# BSE_APPS_Error_Detection.net
KiCad netlist of a schematic drawn in EAGLE
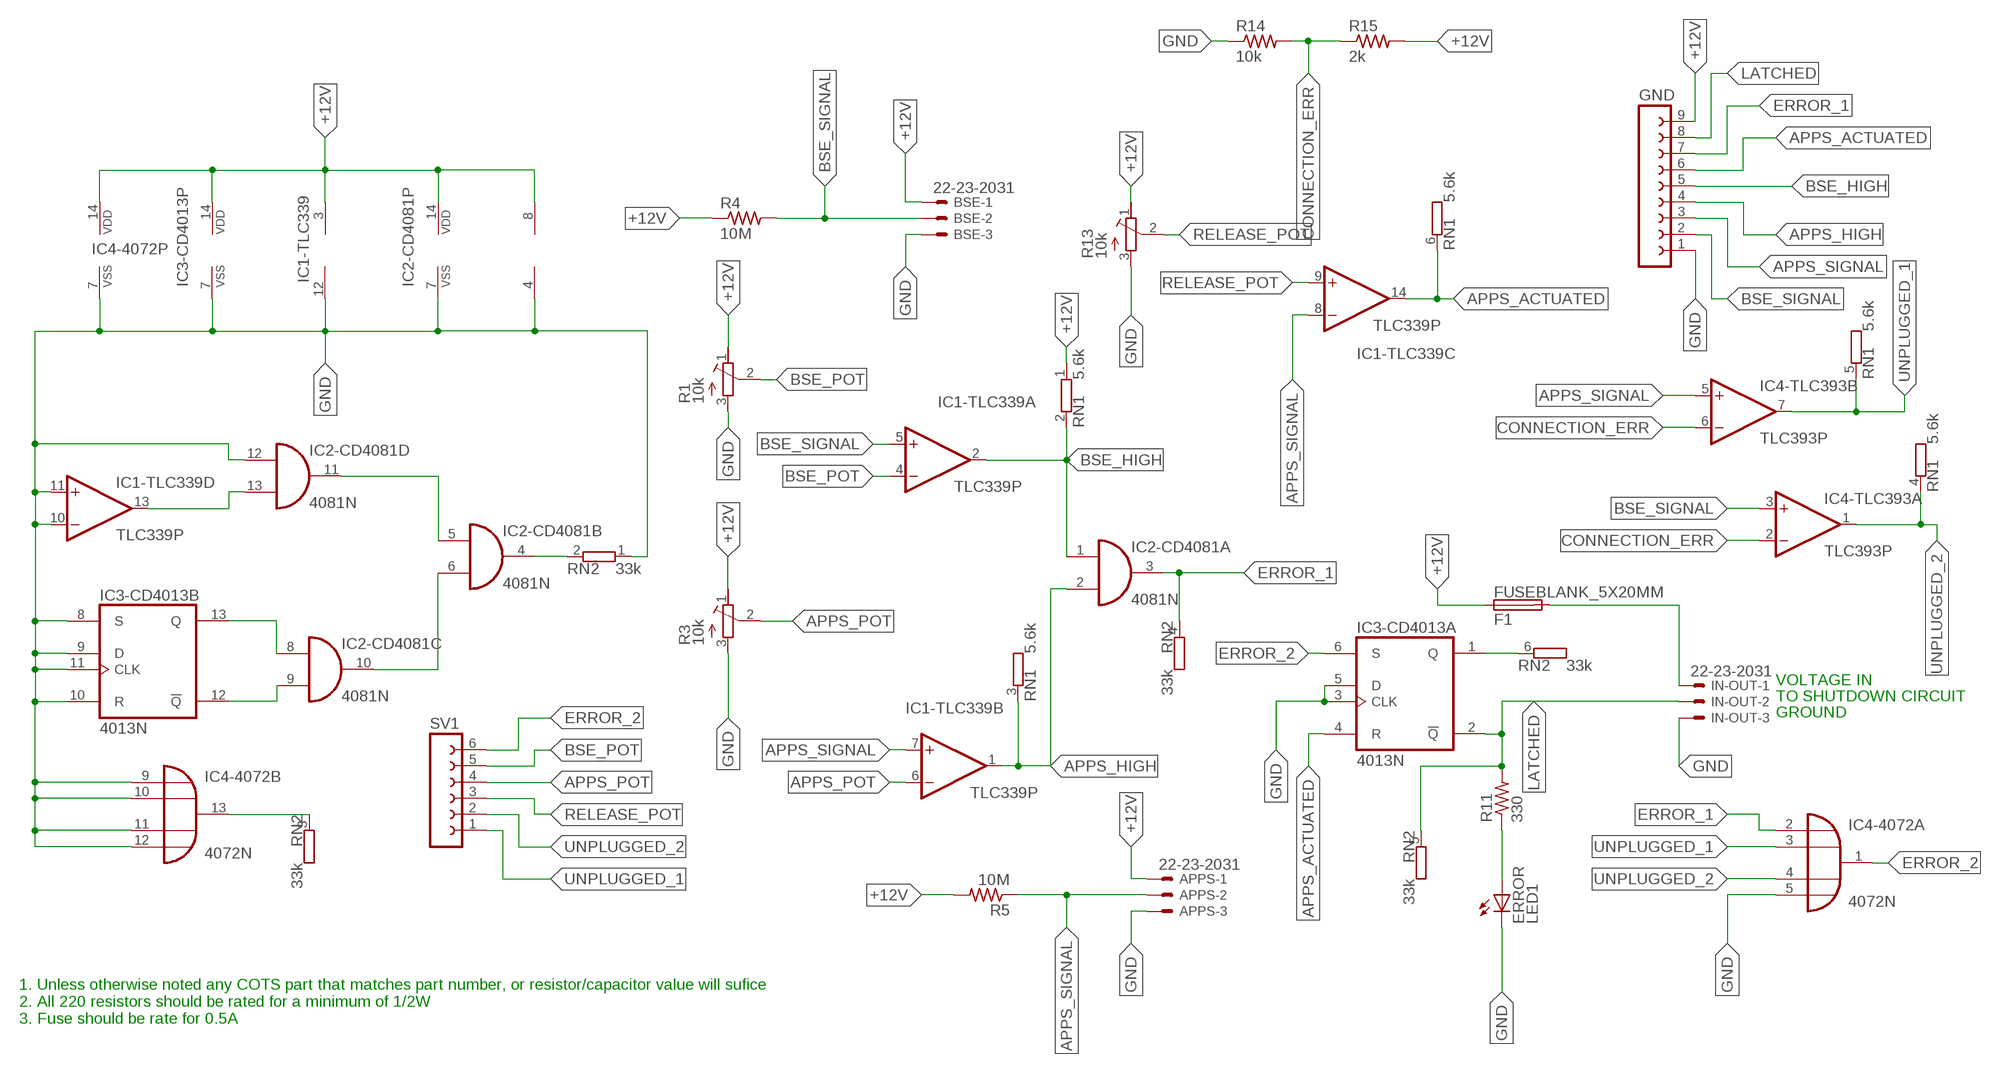
[diagram p0: schematic, sheet 1]

(export (version "E")
  (design (tool "Eeschema 10.0.6"))
  (components
    (comp (ref "APPS")
      (value "22-23-2031")
      (footprint "eagle-import:22-23-2031")
      (fields (field (name "MF") "MOLEX"))
      (libsource (lib "eagle-import") (part "22-23-2031"))
    )
    (comp (ref "BSE")
      (value "22-23-2031")
      (footprint "eagle-import:22-23-2031")
      (fields (field (name "MF") "MOLEX"))
      (libsource (lib "eagle-import") (part "22-23-2031"))
    )
    (comp (ref "ERROR")
      (value "LED1")
      (footprint "eagle-import:LED5MM")
      (libsource (lib "eagle-import") (part "LED5MM"))
    )
    (comp (ref "F1")
      (value "FUSEBLANK_5X20MM")
      (footprint "eagle-import:FUSE_HOLDER_5X20MM")
      (libsource (lib "eagle-import") (part "FUSEBLANK_5X20MM"))
    )
    (comp (ref "GND")
      (value "FE09W")
      (footprint "eagle-import:FE09W")
      (libsource (lib "eagle-import") (part "FE09W"))
    )
    (comp (ref "IC1-TLC339")
      (value "TLC339P")
      (footprint "eagle-import:DIL14")
      (libsource (lib "eagle-import") (part "TLC339P"))
    )
    (comp (ref "IC2-CD4081")
      (value "4081N")
      (footprint "eagle-import:DIL14")
      (libsource (lib "eagle-import") (part "4081N"))
    )
    (comp (ref "IC3-CD4013")
      (value "4013N")
      (footprint "eagle-import:DIL14")
      (libsource (lib "eagle-import") (part "4013N"))
    )
    (comp (ref "IC4-4072")
      (value "4072N")
      (footprint "eagle-import:DIL14")
      (libsource (lib "eagle-import") (part "4072N"))
    )
    (comp (ref "IC4-TLC393")
      (value "TLC393P")
      (footprint "eagle-import:DIL08")
      (libsource (lib "eagle-import") (part "TLC393P"))
    )
    (comp (ref "IN-OUT")
      (value "22-23-2031")
      (footprint "eagle-import:22-23-2031")
      (fields (field (name "MF") "MOLEX"))
      (libsource (lib "eagle-import") (part "22-23-2031"))
    )
    (comp (ref "R1")
      (value "10k")
      (footprint "eagle-import:RTRIM3006P")
      (libsource (lib "eagle-import") (part "R-TRIMM3006P"))
    )
    (comp (ref "R3")
      (value "10k")
      (footprint "eagle-import:RTRIM3006P")
      (libsource (lib "eagle-import") (part "R-TRIMM3006P"))
    )
    (comp (ref "R4")
      (value "10M")
      (footprint "eagle-import:0207_10")
      (libsource (lib "eagle-import") (part "R-US_0207/10"))
    )
    (comp (ref "R5")
      (value "10M")
      (footprint "eagle-import:0207_10")
      (libsource (lib "eagle-import") (part "R-US_0207/10"))
    )
    (comp (ref "R11")
      (value "330")
      (footprint "eagle-import:0207_10")
      (libsource (lib "eagle-import") (part "R-US_0207/10"))
    )
    (comp (ref "R13")
      (value "10k")
      (footprint "eagle-import:RTRIM3006P")
      (libsource (lib "eagle-import") (part "R-TRIMM3006P"))
    )
    (comp (ref "R14")
      (value "10k")
      (footprint "eagle-import:0207_10")
      (libsource (lib "eagle-import") (part "R-US_0207/10"))
    )
    (comp (ref "R15")
      (value "2k")
      (footprint "eagle-import:0207_10")
      (libsource (lib "eagle-import") (part "R-US_0207/10"))
    )
    (comp (ref "RN1")
      (value "5.6k")
      (footprint "eagle-import:SIL6")
      (libsource (lib "eagle-import") (part "GE05RP"))
    )
    (comp (ref "RN2")
      (value "33k")
      (footprint "eagle-import:SIL6")
      (libsource (lib "eagle-import") (part "GE05RP"))
    )
    (comp (ref "SV1")
      (value "FE06W")
      (footprint "eagle-import:FE06W")
      (libsource (lib "eagle-import") (part "FE06W"))
    )
  )
  (nets
    (net (code "1") (name "+12V") (class "Default")
      (node (ref "APPS") (pin "1") (pinfunction "S_1") (pintype "passive"))
      (node (ref "BSE") (pin "1") (pinfunction "S_1") (pintype "passive"))
      (node (ref "F1") (pin "1") (pinfunction "1_1") (pintype "passive"))
      (node (ref "GND") (pin "9") (pinfunction "9_9") (pintype "passive"))
      (node (ref "IC1-TLC339") (pin "3") (pinfunction "V+_3") (pintype "power_in"))
      (node (ref "IC2-CD4081") (pin "14") (pinfunction "VDD_14") (pintype "power_in"))
      (node (ref "IC3-CD4013") (pin "14") (pinfunction "VDD_14") (pintype "power_in"))
      (node (ref "IC4-4072") (pin "14") (pinfunction "VDD_14") (pintype "power_in"))
      (node (ref "IC4-TLC393") (pin "8") (pinfunction "V+_8") (pintype "power_in"))
      (node (ref "R1") (pin "1") (pinfunction "E_1") (pintype "passive"))
      (node (ref "R13") (pin "1") (pinfunction "E_1") (pintype "passive"))
      (node (ref "R15") (pin "2") (pinfunction "2_2") (pintype "passive"))
      (node (ref "R3") (pin "1") (pinfunction "E_1") (pintype "passive"))
      (node (ref "R4") (pin "1") (pinfunction "1_1") (pintype "passive"))
      (node (ref "R5") (pin "2") (pinfunction "2_2") (pintype "passive"))
      (node (ref "RN1") (pin "1") (pinfunction "1_1") (pintype "passive"))
    )
    (net (code "2") (name "APPS_ACTUATED") (class "Default")
      (node (ref "GND") (pin "6") (pinfunction "6_6") (pintype "passive"))
      (node (ref "IC1-TLC339") (pin "14") (pinfunction "OUT_14") (pintype "output"))
      (node (ref "IC3-CD4013") (pin "4") (pinfunction "R_4") (pintype "input"))
      (node (ref "RN1") (pin "6") (pinfunction "2_6") (pintype "passive"))
    )
    (net (code "3") (name "APPS_HIGH") (class "Default")
      (node (ref "GND") (pin "4") (pinfunction "4_4") (pintype "passive"))
      (node (ref "IC1-TLC339") (pin "1") (pinfunction "OUT_1") (pintype "output"))
      (node (ref "IC2-CD4081") (pin "2") (pinfunction "I1_2") (pintype "input"))
      (node (ref "RN1") (pin "3") (pinfunction "2_3") (pintype "passive"))
    )
    (net (code "4") (name "APPS_POT") (class "Default")
      (node (ref "IC1-TLC339") (pin "6") (pinfunction "-IN_6") (pintype "input"))
      (node (ref "R3") (pin "2") (pinfunction "S_2") (pintype "passive"))
      (node (ref "SV1") (pin "4") (pinfunction "4_4") (pintype "passive"))
    )
    (net (code "5") (name "APPS_SIGNAL") (class "Default")
      (node (ref "APPS") (pin "2") (pinfunction "S_2") (pintype "passive"))
      (node (ref "GND") (pin "3") (pinfunction "3_3") (pintype "passive"))
      (node (ref "IC1-TLC339") (pin "7") (pinfunction "+IN_7") (pintype "input"))
      (node (ref "IC1-TLC339") (pin "8") (pinfunction "-IN_8") (pintype "input"))
      (node (ref "IC4-TLC393") (pin "5") (pinfunction "+IN_5") (pintype "input"))
      (node (ref "R5") (pin "1") (pinfunction "1_1") (pintype "passive"))
    )
    (net (code "6") (name "BSE_HIGH") (class "Default")
      (node (ref "GND") (pin "5") (pinfunction "5_5") (pintype "passive"))
      (node (ref "IC1-TLC339") (pin "2") (pinfunction "OUT_2") (pintype "output"))
      (node (ref "IC2-CD4081") (pin "1") (pinfunction "I0_1") (pintype "input"))
      (node (ref "RN1") (pin "2") (pinfunction "2_2") (pintype "passive"))
    )
    (net (code "7") (name "BSE_POT") (class "Default")
      (node (ref "IC1-TLC339") (pin "4") (pinfunction "-IN_4") (pintype "input"))
      (node (ref "R1") (pin "2") (pinfunction "S_2") (pintype "passive"))
      (node (ref "SV1") (pin "5") (pinfunction "5_5") (pintype "passive"))
    )
    (net (code "8") (name "BSE_SIGNAL") (class "Default")
      (node (ref "BSE") (pin "2") (pinfunction "S_2") (pintype "passive"))
      (node (ref "GND") (pin "2") (pinfunction "2_2") (pintype "passive"))
      (node (ref "IC1-TLC339") (pin "5") (pinfunction "+IN_5") (pintype "input"))
      (node (ref "IC4-TLC393") (pin "3") (pinfunction "+IN_3") (pintype "input"))
      (node (ref "R4") (pin "2") (pinfunction "2_2") (pintype "passive"))
    )
    (net (code "9") (name "CONNECTION_ERR") (class "Default")
      (node (ref "IC4-TLC393") (pin "2") (pinfunction "-IN_2") (pintype "input"))
      (node (ref "IC4-TLC393") (pin "6") (pinfunction "-IN_6") (pintype "input"))
      (node (ref "R14") (pin "2") (pinfunction "2_2") (pintype "passive"))
      (node (ref "R15") (pin "1") (pinfunction "1_1") (pintype "passive"))
    )
    (net (code "10") (name "ERROR_1") (class "Default")
      (node (ref "GND") (pin "7") (pinfunction "7_7") (pintype "passive"))
      (node (ref "IC2-CD4081") (pin "3") (pinfunction "O_3") (pintype "output"))
      (node (ref "IC4-4072") (pin "2") (pinfunction "I0_2") (pintype "input"))
      (node (ref "RN2") (pin "4") (pinfunction "2_4") (pintype "passive"))
    )
    (net (code "11") (name "ERROR_2") (class "Default")
      (node (ref "IC3-CD4013") (pin "6") (pinfunction "S_6") (pintype "input"))
      (node (ref "IC4-4072") (pin "1") (pinfunction "O_1") (pintype "output"))
      (node (ref "SV1") (pin "6") (pinfunction "6_6") (pintype "passive"))
    )
    (net (code "12") (name "GND") (class "Default")
      (node (ref "APPS") (pin "3") (pinfunction "S_3") (pintype "passive"))
      (node (ref "BSE") (pin "3") (pinfunction "S_3") (pintype "passive"))
      (node (ref "ERROR") (pin "K") (pinfunction "C_K") (pintype "passive"))
      (node (ref "GND") (pin "1") (pinfunction "1_1") (pintype "passive"))
      (node (ref "IC1-TLC339") (pin "10") (pinfunction "-IN_10") (pintype "input"))
      (node (ref "IC1-TLC339") (pin "11") (pinfunction "+IN_11") (pintype "input"))
      (node (ref "IC1-TLC339") (pin "12") (pinfunction "V-_12") (pintype "power_in"))
      (node (ref "IC2-CD4081") (pin "12") (pinfunction "I0_12") (pintype "input"))
      (node (ref "IC2-CD4081") (pin "7") (pinfunction "VSS_7") (pintype "power_in"))
      (node (ref "IC3-CD4013") (pin "10") (pinfunction "R_10") (pintype "input"))
      (node (ref "IC3-CD4013") (pin "11") (pinfunction "CLK_11") (pintype "input"))
      (node (ref "IC3-CD4013") (pin "3") (pinfunction "CLK_3") (pintype "input"))
      (node (ref "IC3-CD4013") (pin "5") (pinfunction "D_5") (pintype "input"))
      (node (ref "IC3-CD4013") (pin "7") (pinfunction "VSS_7") (pintype "power_in"))
      (node (ref "IC3-CD4013") (pin "8") (pinfunction "S_8") (pintype "input"))
      (node (ref "IC3-CD4013") (pin "9") (pinfunction "D_9") (pintype "input"))
      (node (ref "IC4-4072") (pin "10") (pinfunction "I1_10") (pintype "input"))
      (node (ref "IC4-4072") (pin "11") (pinfunction "I2_11") (pintype "input"))
      (node (ref "IC4-4072") (pin "12") (pinfunction "I3_12") (pintype "input"))
      (node (ref "IC4-4072") (pin "5") (pinfunction "I3_5") (pintype "input"))
      (node (ref "IC4-4072") (pin "7") (pinfunction "VSS_7") (pintype "power_in"))
      (node (ref "IC4-4072") (pin "9") (pinfunction "I0_9") (pintype "input"))
      (node (ref "IC4-TLC393") (pin "4") (pinfunction "V-_4") (pintype "power_in"))
      (node (ref "IN-OUT") (pin "3") (pinfunction "S_3") (pintype "passive"))
      (node (ref "R1") (pin "3") (pinfunction "A_3") (pintype "passive"))
      (node (ref "R13") (pin "3") (pinfunction "A_3") (pintype "passive"))
      (node (ref "R14") (pin "1") (pinfunction "1_1") (pintype "passive"))
      (node (ref "R3") (pin "3") (pinfunction "A_3") (pintype "passive"))
      (node (ref "RN2") (pin "1") (pinfunction "1_1") (pintype "passive"))
    )
    (net (code "13") (name "LATCHED") (class "Default")
      (node (ref "GND") (pin "8") (pinfunction "8_8") (pintype "passive"))
      (node (ref "IC3-CD4013") (pin "2") (pinfunction "~{Q}_2") (pintype "output"))
      (node (ref "IN-OUT") (pin "2") (pinfunction "S_2") (pintype "passive"))
      (node (ref "R11") (pin "2") (pinfunction "2_2") (pintype "passive"))
      (node (ref "RN2") (pin "5") (pinfunction "2_5") (pintype "passive"))
    )
    (net (code "14") (name "Net-(ERROR-PadA)") (class "Default")
      (node (ref "ERROR") (pin "A") (pinfunction "A_A") (pintype "passive"))
      (node (ref "R11") (pin "1") (pinfunction "1_1") (pintype "passive"))
    )
    (net (code "15") (name "Net-(IC1-TLC339D-OUT)") (class "Default")
      (node (ref "IC1-TLC339") (pin "13") (pinfunction "OUT_13") (pintype "output"))
      (node (ref "IC2-CD4081") (pin "13") (pinfunction "I1_13") (pintype "input"))
    )
    (net (code "16") (name "Net-(IC2-CD4081B-I0)") (class "Default")
      (node (ref "IC2-CD4081") (pin "11") (pinfunction "O_11") (pintype "output"))
      (node (ref "IC2-CD4081") (pin "5") (pinfunction "I0_5") (pintype "input"))
    )
    (net (code "17") (name "Net-(IC2-CD4081B-I1)") (class "Default")
      (node (ref "IC2-CD4081") (pin "10") (pinfunction "O_10") (pintype "output"))
      (node (ref "IC2-CD4081") (pin "6") (pinfunction "I1_6") (pintype "input"))
    )
    (net (code "18") (name "Net-(IC2-CD4081B-O)") (class "Default")
      (node (ref "IC2-CD4081") (pin "4") (pinfunction "O_4") (pintype "output"))
      (node (ref "RN2") (pin "2") (pinfunction "2_2") (pintype "passive"))
    )
    (net (code "19") (name "Net-(IC2-CD4081C-I0)") (class "Default")
      (node (ref "IC2-CD4081") (pin "8") (pinfunction "I0_8") (pintype "input"))
      (node (ref "IC3-CD4013") (pin "13") (pinfunction "Q_13") (pintype "output"))
    )
    (net (code "20") (name "Net-(IC2-CD4081C-I1)") (class "Default")
      (node (ref "IC2-CD4081") (pin "9") (pinfunction "I1_9") (pintype "input"))
      (node (ref "IC3-CD4013") (pin "12") (pinfunction "~{Q}_12") (pintype "output"))
    )
    (net (code "21") (name "Net-(IC3-CD4013A-Q)") (class "Default")
      (node (ref "IC3-CD4013") (pin "1") (pinfunction "Q_1") (pintype "output"))
      (node (ref "RN2") (pin "6") (pinfunction "2_6") (pintype "passive"))
    )
    (net (code "22") (name "Net-(IC4-4072B-O)") (class "Default")
      (node (ref "IC4-4072") (pin "13") (pinfunction "O_13") (pintype "output"))
      (node (ref "RN2") (pin "3") (pinfunction "2_3") (pintype "passive"))
    )
    (net (code "23") (name "Net-(IN-OUTA-S)") (class "Default")
      (node (ref "F1") (pin "2") (pinfunction "2_2") (pintype "passive"))
      (node (ref "IN-OUT") (pin "1") (pinfunction "S_1") (pintype "passive"))
    )
    (net (code "24") (name "RELEASE_POT") (class "Default")
      (node (ref "IC1-TLC339") (pin "9") (pinfunction "+IN_9") (pintype "input"))
      (node (ref "R13") (pin "2") (pinfunction "S_2") (pintype "passive"))
      (node (ref "SV1") (pin "3") (pinfunction "3_3") (pintype "passive"))
    )
    (net (code "25") (name "UNPLUGGED_1") (class "Default")
      (node (ref "IC4-4072") (pin "3") (pinfunction "I1_3") (pintype "input"))
      (node (ref "IC4-TLC393") (pin "7") (pinfunction "OUT_7") (pintype "output"))
      (node (ref "RN1") (pin "5") (pinfunction "2_5") (pintype "passive"))
      (node (ref "SV1") (pin "1") (pinfunction "1_1") (pintype "passive"))
    )
    (net (code "26") (name "UNPLUGGED_2") (class "Default")
      (node (ref "IC4-4072") (pin "4") (pinfunction "I2_4") (pintype "input"))
      (node (ref "IC4-TLC393") (pin "1") (pinfunction "OUT_1") (pintype "output"))
      (node (ref "RN1") (pin "4") (pinfunction "2_4") (pintype "passive"))
      (node (ref "SV1") (pin "2") (pinfunction "2_2") (pintype "passive"))
    )
  )
)
